# USB.net
KiCad netlist of a schematic drawn in Altium Designer
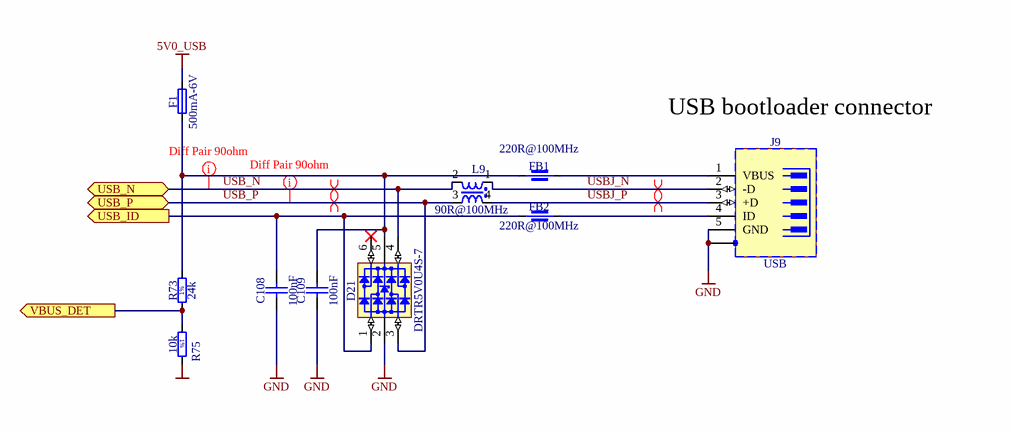
[diagram p0: USB.SchDoc]

(export (version "E")
  (design (tool "Eeschema 10.0.6"))
  (components
    (comp (ref "C108")
      (value "100nF")
      (footprint "CAPC1005X55N")
      (description "Non-polarised capacitor")
      (fields
        (field (name "PART NUMBER") "CC0402_100NF_16V_10%_X7R")
        (field (name "VOLTAGE") "16V")
        (field (name "AUTHOR") "CERN DEM JLC")
      )
      (libsource (lib "Capacitors") (part "Capacitor - non polarized"))
    )
    (comp (ref "C109")
      (value "100nF")
      (footprint "CAPC1005X55N")
      (description "Non-polarised capacitor")
      (fields
        (field (name "PART NUMBER") "CC0402_100NF_16V_10%_X7R")
        (field (name "VOLTAGE") "16V")
        (field (name "AUTHOR") "CERN DEM JLC")
      )
      (libsource (lib "Capacitors") (part "Capacitor - non polarized"))
    )
    (comp (ref "D21")
      (value "DRTR5V0U4S-7")
      (footprint "SOT65P210X110-6N")
      (description "Integrated Quad Ultra-Low Capacitance ESD Protection")
      (fields (field (name "MANUFACTURER") "DIODES") (field (name "AUTHOR") "GK"))
      (libsource (lib "Diodes") (part "D_TVS_DRTR5V0U4S-7"))
    )
    (comp (ref "F1")
      (value "500mA-6V")
      (footprint "FUSR_BOURNS_MF-PSMF050")
      (description "Fuse")
      (fields
        (field (name "PART NUMBER") "FUSR_BOURNS_MF-PSMF050X-2")
        (field (name "MANUFACTURER") "BOURNS")
        (field (name "AUTHOR") "CERN DEM MR")
      )
      (libsource (lib "Eletro-mechanical") (part "Fuse"))
    )
    (comp (ref "FB1")
      (value "220R@100MHz")
      (footprint "INDC1005X55N")
      (fields
        (field (name "PART NUMBER") "IND0402_MURATA_BLM15HB221SN1")
        (field (name "POWER") "250mA")
        (field (name "TOLERANCE") "±25%")
        (field (name "AUTHOR") "CERN DEM JLC")
      )
      (libsource (lib "Inductors & Transformers") (part "Ferrite Bead"))
    )
    (comp (ref "FB2")
      (value "220R@100MHz")
      (footprint "INDC1005X55N")
      (fields
        (field (name "PART NUMBER") "IND0402_MURATA_BLM15HB221SN1")
        (field (name "POWER") "250mA")
        (field (name "TOLERANCE") "±25%")
        (field (name "AUTHOR") "CERN DEM JLC")
      )
      (libsource (lib "Inductors & Transformers") (part "Ferrite Bead"))
    )
    (comp (ref "J9")
      (value "USB")
      (footprint "UJ2-MIBH-4-MSMT")
      (description "5 Pin + 1 Shield  in-line USB Receptacle")
      (fields
        (field (name "PART NUMBER") "CUI_UJ2-MIBH-4-MSMT")
        (field (name "MANUFACTURER") "CUI")
        (field (name "AUTHOR") "GK")
      )
      (libsource (lib "LIBRARY_SCH") (part "CON_USB_UJ2-MIBH-4-MSMT"))
    )
    (comp (ref "L9")
      (value "90R@100MHz")
      (footprint "IND_MURATA_DLW21S")
      (description "Inductor Common Mode")
      (fields
        (field (name "PART NUMBER") "IND_MURATA_DLW21SN900SQ2L")
        (field (name "POWER") "330mA")
        (field (name "AUTHOR") "CERN DEM JLC")
      )
      (libsource (lib "Inductors & Transformers") (part "Inductor Common Mode 1Dot-2 4Dot-3"))
    )
    (comp (ref "R73")
      (value "24k")
      (footprint "RESC1608X55N")
      (description "Resistor - 1%")
      (fields
        (field (name "PART NUMBER") "R0603_24K_1%_0.1W_100PPM")
        (field (name "POWER") "0.1W")
        (field (name "AUTHOR") "CERN DEM JLC")
      )
      (libsource (lib "Resistors") (part "Resistor - 1%"))
    )
    (comp (ref "R75")
      (value "10k")
      (footprint "RESC1005X40N")
      (description "Resistor - 1%")
      (fields
        (field (name "PART NUMBER") "R0402_10K_1%_0.0625W_100PPM")
        (field (name "POWER") "0.0625W")
        (field (name "AUTHOR") "CERN DEM JLC")
      )
      (libsource (lib "Resistors") (part "Resistor - 1%"))
    )
  )
  (nets
    (net (code "1") (name "/USBJ_N") (class "Default")
      (node (ref "J9") (pin "2") (pinfunction "-D_2") (pintype "bidirectional"))
      (node (ref "L9") (pin "1") (pinfunction "1_1") (pintype "passive"))
    )
    (net (code "2") (name "/USBJ_P") (class "Default")
      (node (ref "J9") (pin "3") (pinfunction "+D_3") (pintype "bidirectional"))
      (node (ref "L9") (pin "4") (pinfunction "4_4") (pintype "passive"))
    )
    (net (code "3") (name "/USB_ID") (class "Default")
      (node (ref "C108") (pin "2") (pinfunction "2_2") (pintype "passive"))
      (node (ref "D21") (pin "1") (pinfunction "I/O1_1") (pintype "bidirectional"))
      (node (ref "FB2") (pin "1") (pinfunction "1_1") (pintype "passive"))
    )
    (net (code "4") (name "/USB_N") (class "Default")
      (node (ref "D21") (pin "4") (pinfunction "I/O3_4") (pintype "bidirectional"))
      (node (ref "L9") (pin "2") (pinfunction "2_2") (pintype "passive"))
    )
    (net (code "5") (name "/USB_P") (class "Default")
      (node (ref "D21") (pin "3") (pinfunction "I/O2_3") (pintype "bidirectional"))
      (node (ref "L9") (pin "3") (pinfunction "3_3") (pintype "passive"))
    )
    (net (code "6") (name "/VBUS_DET") (class "Default")
      (node (ref "R73") (pin "1") (pinfunction "1_1") (pintype "passive"))
      (node (ref "R75") (pin "1") (pinfunction "1_1") (pintype "passive"))
    )
    (net (code "7") (name "5V0_USB") (class "Default")
      (node (ref "F1") (pin "2") (pinfunction "2_2") (pintype "passive"))
    )
    (net (code "8") (name "GND") (class "Default")
      (node (ref "C108") (pin "1") (pinfunction "1_1") (pintype "passive"))
      (node (ref "C109") (pin "1") (pinfunction "1_1") (pintype "passive"))
      (node (ref "D21") (pin "2") (pinfunction "GND_2") (pintype "power_in"))
      (node (ref "J9") (pin "10") (pinfunction "SH_10") (pintype "power_in"))
      (node (ref "J9") (pin "11") (pinfunction "SH_11") (pintype "power_in"))
      (node (ref "J9") (pin "5") (pinfunction "GND_5") (pintype "power_in"))
      (node (ref "J9") (pin "6") (pinfunction "SH_6") (pintype "power_in"))
      (node (ref "J9") (pin "7") (pinfunction "SH_7") (pintype "power_in"))
      (node (ref "J9") (pin "8") (pinfunction "SH_8") (pintype "power_in"))
      (node (ref "J9") (pin "9") (pinfunction "SH_9") (pintype "power_in"))
      (node (ref "R75") (pin "2") (pinfunction "2_2") (pintype "passive"))
    )
    (net (code "9") (name "Net-(D21-VBUS)") (class "Default")
      (node (ref "C109") (pin "2") (pinfunction "2_2") (pintype "passive"))
      (node (ref "D21") (pin "5") (pinfunction "VBUS_5") (pintype "power_in"))
      (node (ref "F1") (pin "1") (pinfunction "1_1") (pintype "passive"))
      (node (ref "FB1") (pin "1") (pinfunction "1_1") (pintype "passive"))
      (node (ref "R73") (pin "2") (pinfunction "2_2") (pintype "passive"))
    )
    (net (code "10") (name "Net-(J9-ID)") (class "Default")
      (node (ref "FB2") (pin "2") (pinfunction "2_2") (pintype "passive"))
      (node (ref "J9") (pin "4") (pinfunction "ID_4") (pintype "passive"))
    )
    (net (code "11") (name "Net-(J9-VBUS)") (class "Default")
      (node (ref "FB1") (pin "2") (pinfunction "2_2") (pintype "passive"))
      (node (ref "J9") (pin "1") (pinfunction "VBUS_1") (pintype "power_in"))
    )
    (net (code "12") (name "unconnected-(D21-I{slash}O4-Pad6)") (class "Default")
      (node (ref "D21") (pin "6") (pinfunction "I/O4_6") (pintype "bidirectional+no_connect"))
    )
  )
)
